# openSX70_ALPHA_V6-2-5-20181220.net
KiCad netlist of a schematic drawn in EAGLE
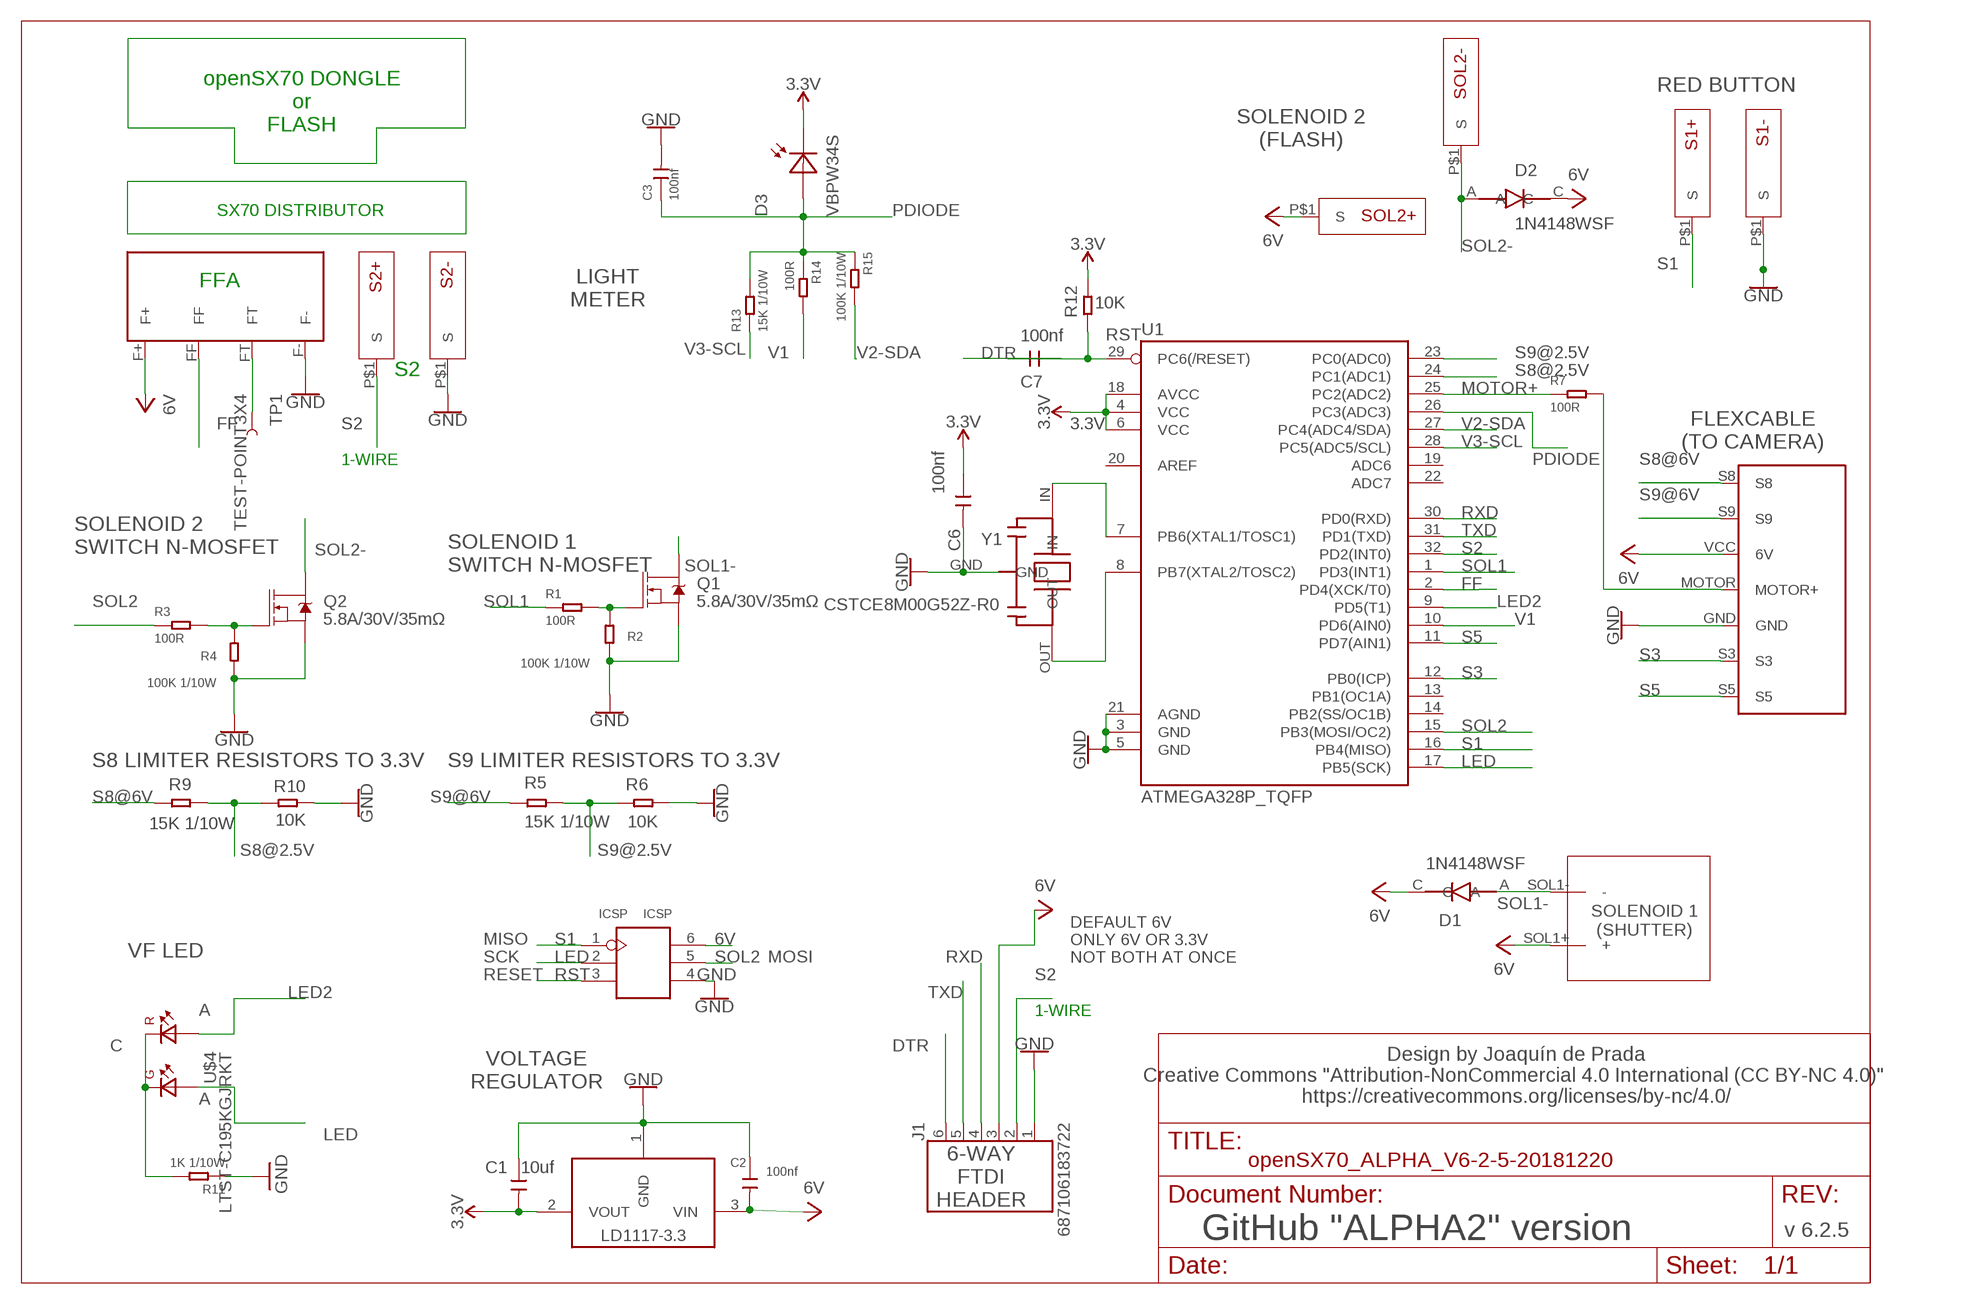
[diagram p0: schematic, sheet 1]

(export (version "E")
  (design (tool "Eeschema 10.0.6"))
  (components
    (comp (ref "C1")
      (value "10uf")
      (footprint "eagle-import:C0603")
      (fields (field (name "MPN") "CC0603KRX5R6BB106"))
      (libsource (lib "eagle-import") (part "CERAMIC-10UF-10V-10%-X5R(0603)"))
    )
    (comp (ref "C2")
      (value "100nf")
      (footprint "eagle-import:C0603")
      (fields (field (name "MPN") "CC0603KRX7R9BB104"))
      (libsource (lib "eagle-import") (part "CERAMIC-100NF-50V-10%-X7R(0603)"))
    )
    (comp (ref "C3")
      (value "100nf")
      (footprint "eagle-import:C0603")
      (fields (field (name "MPN") "CC0603KRX7R9BB104"))
      (libsource (lib "eagle-import") (part "CERAMIC-100NF-50V-10%-X7R(0603)"))
    )
    (comp (ref "C6")
      (value "100nf")
      (footprint "eagle-import:C0603")
      (fields (field (name "MPN") "CC0603KRX7R9BB104"))
      (libsource (lib "eagle-import") (part "CERAMIC-100NF-50V-10%-X7R(0603)"))
    )
    (comp (ref "C7")
      (value "100nf")
      (footprint "eagle-import:C0603")
      (fields (field (name "MPN") "CC0603KRX7R9BB104"))
      (libsource (lib "eagle-import") (part "CERAMIC-100NF-50V-10%-X7R(0603)"))
    )
    (comp (ref "D1")
      (value "1N4148WSF")
      (footprint "eagle-import:SODFL2512X100N")
      (fields (field (name "MANUFACTURER") "Fairchild Semiconductor"))
      (libsource (lib "eagle-import") (part "1N4148WS"))
    )
    (comp (ref "D2")
      (value "1N4148WSF")
      (footprint "eagle-import:SODFL2512X100N")
      (fields (field (name "MANUFACTURER") "Fairchild Semiconductor"))
      (libsource (lib "eagle-import") (part "1N4148WS"))
    )
    (comp (ref "D3")
      (value "VBPW34S")
      (footprint "eagle-import:SOD6439X130N")
      (fields (field (name "DIGI-KEY_PART_NUMBER") "751-1500-1-ND") (field (name "MF") "Vishay"))
      (libsource (lib "eagle-import") (part "VBPW34S"))
    )
    (comp (ref "ICSP")
      (value "ICSP")
      (footprint "eagle-import:H2X3-2.54")
      (libsource (lib "eagle-import") (part "ICSP"))
    )
    (comp (ref "J1")
      (value "687106183722")
      (footprint "eagle-import:687106183722")
      (fields (field (name "MF") "Wurth Electronics"))
      (libsource (lib "eagle-import") (part "687106183722"))
    )
    (comp (ref "LD11172.5V")
      (value "LD1117 2.5V")
      (footprint "eagle-import:SOT223")
      (fields (field (name "MF") "Advanced Monolithic Systems") (field (name "MP") "AMS1117-5.0"))
      (libsource (lib "eagle-import") (part "LD1117-3.3"))
    )
    (comp (ref "Q1")
      (value "5.8A/30V/35mΩ")
      (footprint "eagle-import:SOT23-3")
      (libsource (lib "eagle-import") (part "MOSFET-NCH-AO3404A"))
    )
    (comp (ref "Q2")
      (value "5.8A/30V/35mΩ")
      (footprint "eagle-import:SOT23-3")
      (libsource (lib "eagle-import") (part "MOSFET-NCH-AO3404A"))
    )
    (comp (ref "R1")
      (value "100R")
      (footprint "eagle-import:R0603")
      (fields (field (name "MPN") "RC0603JR-07100RL"))
      (libsource (lib "eagle-import") (part "SMD-RES-100R-5%-1/10W(0603)"))
    )
    (comp (ref "R2")
      (value "100K 1/10W")
      (footprint "eagle-import:R0603")
      (fields (field (name "MPN") "RC0603JR-07100KL"))
      (libsource (lib "eagle-import") (part "SMD-RES-100K-5%-1/10W(0603)"))
    )
    (comp (ref "R3")
      (value "100R")
      (footprint "eagle-import:R0603")
      (fields (field (name "MPN") "RC0603JR-07100RL"))
      (libsource (lib "eagle-import") (part "SMD-RES-100R-5%-1/10W(0603)"))
    )
    (comp (ref "R4")
      (value "100K 1/10W")
      (footprint "eagle-import:R0603")
      (fields (field (name "MPN") "RC0603JR-07100KL"))
      (libsource (lib "eagle-import") (part "SMD-RES-100K-5%-1/10W(0603)"))
    )
    (comp (ref "R5")
      (value "15K 1/10W")
      (footprint "eagle-import:R0603")
      (fields (field (name "MPN") "RC0603FR-0715KL"))
      (libsource (lib "eagle-import") (part "SMD-RES-15K-1%-1/10W(0603)"))
    )
    (comp (ref "R6")
      (value "10K")
      (footprint "eagle-import:R0603")
      (fields (field (name "MPN") "RC0603FR-0710KL"))
      (libsource (lib "eagle-import") (part "SMD-RES-10K-1%-1/10W(0603)"))
    )
    (comp (ref "R7")
      (value "100R")
      (footprint "eagle-import:R0603")
      (fields (field (name "MPN") "RC0603JR-07100RL"))
      (libsource (lib "eagle-import") (part "SMD-RES-100R-5%-1/10W(0603)"))
    )
    (comp (ref "R9")
      (value "15K 1/10W")
      (footprint "eagle-import:R0603")
      (fields (field (name "MPN") "RC0603FR-0715KL"))
      (libsource (lib "eagle-import") (part "SMD-RES-15K-1%-1/10W(0603)"))
    )
    (comp (ref "R10")
      (value "10K")
      (footprint "eagle-import:R0603")
      (fields (field (name "MPN") "RC0603FR-0710KL"))
      (libsource (lib "eagle-import") (part "SMD-RES-10K-1%-1/10W(0603)"))
    )
    (comp (ref "R11")
      (value "1K 1/10W")
      (footprint "eagle-import:R0603")
      (fields (field (name "MPN") "RC0603JR-071KL"))
      (libsource (lib "eagle-import") (part "SMD-RES-1K-5%-1/10W(0603)"))
    )
    (comp (ref "R12")
      (value "10K")
      (footprint "eagle-import:R0603")
      (fields (field (name "MPN") "RC0603FR-0710KL"))
      (libsource (lib "eagle-import") (part "SMD-RES-10K-1%-1/10W(0603)"))
    )
    (comp (ref "R13")
      (value "15K 1/10W")
      (footprint "eagle-import:R0603")
      (fields (field (name "MPN") "RC0603FR-0715KL"))
      (libsource (lib "eagle-import") (part "SMD-RES-15K-1%-1/10W(0603)"))
    )
    (comp (ref "R14")
      (value "100R")
      (footprint "eagle-import:R0603")
      (fields (field (name "MPN") "RC0603JR-07100RL"))
      (libsource (lib "eagle-import") (part "SMD-RES-100R-5%-1/10W(0603)"))
    )
    (comp (ref "R15")
      (value "100K 1/10W")
      (footprint "eagle-import:R0603")
      (fields (field (name "MPN") "RC0603JR-07100KL"))
      (libsource (lib "eagle-import") (part "SMD-RES-100K-5%-1/10W(0603)"))
    )
    (comp (ref "S1+")
      (value "SX70-S-PAD-NEW")
      (footprint "eagle-import:SX70-S-PAD2")
      (libsource (lib "eagle-import") (part "SX70-S-PAD-NEW"))
    )
    (comp (ref "S1-")
      (value "SX70-S-PAD-NEW")
      (footprint "eagle-import:SX70-S-PAD2")
      (libsource (lib "eagle-import") (part "SX70-S-PAD-NEW"))
    )
    (comp (ref "S2+")
      (value "SX70-S-PAD-NEW")
      (footprint "eagle-import:SX70-S-PAD2")
      (libsource (lib "eagle-import") (part "SX70-S-PAD-NEW"))
    )
    (comp (ref "S2-")
      (value "SX70-S-PAD-NEW")
      (footprint "eagle-import:SX70-S-PAD2")
      (libsource (lib "eagle-import") (part "SX70-S-PAD-NEW"))
    )
    (comp (ref "SOL1")
      (value "SX70-SOLENOID1-2PADS")
      (footprint "eagle-import:SX70-SOLENOID1-2")
      (libsource (lib "eagle-import") (part "SX70-SOLENOID1-2PADS"))
    )
    (comp (ref "SOL2+")
      (value "SX70-S-PAD-NEW")
      (footprint "eagle-import:SX70-S-PAD2")
      (libsource (lib "eagle-import") (part "SX70-S-PAD-NEW"))
    )
    (comp (ref "SOL2-")
      (value "SX70-S-PAD-NEW")
      (footprint "eagle-import:SX70-S-PAD2")
      (libsource (lib "eagle-import") (part "SX70-S-PAD-NEW"))
    )
    (comp (ref "TP1")
      (value "TEST-POINT3X4")
      (footprint "eagle-import:PAD.03X.04")
      (libsource (lib "eagle-import") (part "TEST-POINT3X4"))
    )
    (comp (ref "U$1")
      (value "SX70-7-PAD")
      (footprint "eagle-import:SX70-7-PAD-PROPER")
      (libsource (lib "eagle-import") (part "SX70-7-PAD"))
    )
    (comp (ref "U$2")
      (value "FFA")
      (footprint "eagle-import:FFA-PAD-PACKAGE")
      (libsource (lib "eagle-import") (part "SX70-FFA-PAD"))
    )
    (comp (ref "U$4")
      (value "LTST-C195KGJRKT")
      (footprint "eagle-import:LTST-BILED-15X16")
      (fields (field (name "MF") "Lite-On Inc."))
      (libsource (lib "eagle-import") (part "LTST-C195KGJRKT"))
    )
    (comp (ref "U1")
      (value "ATMEGA328P_TQFP")
      (footprint "eagle-import:TQFP32-08")
      (libsource (lib "eagle-import") (part "ATMEGA328P_TQFP"))
    )
    (comp (ref "Y1")
      (value "CSTCE8M00G52Z-R0")
      (footprint "eagle-import:CFP95P160X100-3N")
      (fields (field (name "MF") "Murata") (field (name "MP") "CSTCE16M0V53-R0"))
      (libsource (lib "eagle-import") (part "CSTCE16M0V53-R0"))
    )
  )
  (nets
    (net (code "1") (name "/DTR") (class "Default")
      (node (ref "C7") (pin "1") (pinfunction "1_1") (pintype "passive"))
      (node (ref "J1") (pin "6") (pinfunction "1_6") (pintype "passive"))
    )
    (net (code "2") (name "/FF") (class "Default")
      (node (ref "U$2") (pin "FF") (pinfunction "FF_FF") (pintype "bidirectional"))
      (node (ref "U1") (pin "2") (pinfunction "PD4(XCK/T0)_2") (pintype "bidirectional"))
    )
    (net (code "3") (name "/LED") (class "Default")
      (node (ref "ICSP") (pin "2") (pinfunction "SCK_2") (pintype "bidirectional"))
      (node (ref "U$4") (pin "P$1") (pinfunction "A1_P$1") (pintype "passive"))
      (node (ref "U1") (pin "17") (pinfunction "PB5(SCK)_17") (pintype "bidirectional"))
    )
    (net (code "4") (name "/LED2") (class "Default")
      (node (ref "U$4") (pin "P$2") (pinfunction "A2_P$2") (pintype "passive"))
      (node (ref "U1") (pin "9") (pinfunction "PD5(T1)_9") (pintype "bidirectional"))
    )
    (net (code "5") (name "/MOTOR+") (class "Default")
      (node (ref "R7") (pin "1") (pinfunction "1_1") (pintype "passive"))
      (node (ref "U1") (pin "25") (pinfunction "PC2(ADC2)_25") (pintype "bidirectional"))
    )
    (net (code "6") (name "/PDIODE") (class "Default")
      (node (ref "C3") (pin "1") (pinfunction "1_1") (pintype "passive"))
      (node (ref "D3") (pin "A") (pinfunction "A_A") (pintype "passive"))
      (node (ref "R13") (pin "2") (pinfunction "2_2") (pintype "passive"))
      (node (ref "R14") (pin "1") (pinfunction "1_1") (pintype "passive"))
      (node (ref "R15") (pin "1") (pinfunction "1_1") (pintype "passive"))
      (node (ref "U1") (pin "26") (pinfunction "PC3(ADC3)_26") (pintype "bidirectional"))
    )
    (net (code "7") (name "/RST") (class "Default")
      (node (ref "C7") (pin "2") (pinfunction "2_2") (pintype "passive"))
      (node (ref "ICSP") (pin "3") (pinfunction "RST_3") (pintype "bidirectional"))
      (node (ref "R12") (pin "1") (pinfunction "1_1") (pintype "passive"))
      (node (ref "U1") (pin "29") (pinfunction "PC6(/RESET)_29") (pintype "bidirectional"))
    )
    (net (code "8") (name "/RXD") (class "Default")
      (node (ref "J1") (pin "4") (pinfunction "3_4") (pintype "passive"))
      (node (ref "U1") (pin "30") (pinfunction "PD0(RXD)_30") (pintype "bidirectional"))
    )
    (net (code "9") (name "/S1") (class "Default")
      (node (ref "ICSP") (pin "1") (pinfunction "MISO_1") (pintype "bidirectional"))
      (node (ref "S1+") (pin "P$1") (pinfunction "S_P$1") (pintype "bidirectional"))
      (node (ref "U1") (pin "16") (pinfunction "PB4(MISO)_16") (pintype "bidirectional"))
    )
    (net (code "10") (name "/S2") (class "Default")
      (node (ref "J1") (pin "2") (pinfunction "5_2") (pintype "passive"))
      (node (ref "S2+") (pin "P$1") (pinfunction "S_P$1") (pintype "bidirectional"))
      (node (ref "U1") (pin "32") (pinfunction "PD2(INT0)_32") (pintype "bidirectional"))
    )
    (net (code "11") (name "/S3") (class "Default")
      (node (ref "U$1") (pin "S3") (pinfunction "S3_S3") (pintype "bidirectional"))
      (node (ref "U1") (pin "12") (pinfunction "PB0(ICP)_12") (pintype "bidirectional"))
    )
    (net (code "12") (name "/S5") (class "Default")
      (node (ref "U$1") (pin "S5") (pinfunction "S5_S5") (pintype "bidirectional"))
      (node (ref "U1") (pin "11") (pinfunction "PD7(AIN1)_11") (pintype "bidirectional"))
    )
    (net (code "13") (name "/S8@2.5V") (class "Default")
      (node (ref "R10") (pin "1") (pinfunction "1_1") (pintype "passive"))
      (node (ref "R9") (pin "2") (pinfunction "2_2") (pintype "passive"))
      (node (ref "U1") (pin "24") (pinfunction "PC1(ADC1)_24") (pintype "bidirectional"))
    )
    (net (code "14") (name "/S8@6V") (class "Default")
      (node (ref "R9") (pin "1") (pinfunction "1_1") (pintype "passive"))
      (node (ref "U$1") (pin "S8") (pinfunction "S8_S8") (pintype "bidirectional"))
    )
    (net (code "15") (name "/S9@2.5V") (class "Default")
      (node (ref "R5") (pin "2") (pinfunction "2_2") (pintype "passive"))
      (node (ref "R6") (pin "1") (pinfunction "1_1") (pintype "passive"))
      (node (ref "U1") (pin "23") (pinfunction "PC0(ADC0)_23") (pintype "bidirectional"))
    )
    (net (code "16") (name "/S9@6V") (class "Default")
      (node (ref "R5") (pin "1") (pinfunction "1_1") (pintype "passive"))
      (node (ref "U$1") (pin "S9") (pinfunction "S9_S9") (pintype "bidirectional"))
    )
    (net (code "17") (name "/SOL1") (class "Default")
      (node (ref "R1") (pin "1") (pinfunction "1_1") (pintype "passive"))
      (node (ref "U1") (pin "1") (pinfunction "PD3(INT1)_1") (pintype "bidirectional"))
    )
    (net (code "18") (name "/SOL1-") (class "Default")
      (node (ref "D1") (pin "A") (pinfunction "A_A") (pintype "passive"))
      (node (ref "Q1") (pin "3") (pinfunction "D_3") (pintype "bidirectional"))
      (node (ref "SOL1") (pin "SOL1-") (pinfunction "-_SOL1-") (pintype "bidirectional"))
    )
    (net (code "19") (name "/SOL2") (class "Default")
      (node (ref "ICSP") (pin "5") (pinfunction "MOSI_5") (pintype "bidirectional"))
      (node (ref "R3") (pin "1") (pinfunction "1_1") (pintype "passive"))
      (node (ref "U1") (pin "15") (pinfunction "PB3(MOSI/OC2)_15") (pintype "bidirectional"))
    )
    (net (code "20") (name "/SOL2-") (class "Default")
      (node (ref "D2") (pin "A") (pinfunction "A_A") (pintype "passive"))
      (node (ref "Q2") (pin "3") (pinfunction "D_3") (pintype "bidirectional"))
      (node (ref "SOL2-") (pin "P$1") (pinfunction "S_P$1") (pintype "bidirectional"))
    )
    (net (code "21") (name "/TXD") (class "Default")
      (node (ref "J1") (pin "5") (pinfunction "2_5") (pintype "passive"))
      (node (ref "U1") (pin "31") (pinfunction "PD1(TXD)_31") (pintype "bidirectional"))
    )
    (net (code "22") (name "/V1") (class "Default")
      (node (ref "R14") (pin "2") (pinfunction "2_2") (pintype "passive"))
      (node (ref "U1") (pin "10") (pinfunction "PD6(AIN0)_10") (pintype "bidirectional"))
    )
    (net (code "23") (name "/V2-SDA") (class "Default")
      (node (ref "R15") (pin "2") (pinfunction "2_2") (pintype "passive"))
      (node (ref "U1") (pin "27") (pinfunction "PC4(ADC4/SDA)_27") (pintype "bidirectional"))
    )
    (net (code "24") (name "/V3-SCL") (class "Default")
      (node (ref "R13") (pin "1") (pinfunction "1_1") (pintype "passive"))
      (node (ref "U1") (pin "28") (pinfunction "PC5(ADC5/SCL)_28") (pintype "bidirectional"))
    )
    (net (code "25") (name "3.3V") (class "Default")
      (node (ref "C1") (pin "2") (pinfunction "2_2") (pintype "passive"))
      (node (ref "C6") (pin "1") (pinfunction "1_1") (pintype "passive"))
      (node (ref "D3") (pin "C") (pinfunction "C_C") (pintype "passive"))
      (node (ref "LD11172.5V") (pin "2") (pinfunction "VOUT_2") (pintype "bidirectional"))
      (node (ref "R12") (pin "2") (pinfunction "2_2") (pintype "passive"))
      (node (ref "U1") (pin "18") (pinfunction "AVCC_18") (pintype "bidirectional"))
      (node (ref "U1") (pin "4") (pinfunction "VCC_4") (pintype "bidirectional"))
      (node (ref "U1") (pin "6") (pinfunction "VCC_6") (pintype "bidirectional"))
    )
    (net (code "26") (name "6V") (class "Default")
      (node (ref "C2") (pin "2") (pinfunction "2_2") (pintype "passive"))
      (node (ref "D1") (pin "C") (pinfunction "C_C") (pintype "passive"))
      (node (ref "D2") (pin "C") (pinfunction "C_C") (pintype "passive"))
      (node (ref "ICSP") (pin "6") (pinfunction "VCC_6") (pintype "bidirectional"))
      (node (ref "J1") (pin "3") (pinfunction "4_3") (pintype "passive"))
      (node (ref "LD11172.5V") (pin "3") (pinfunction "VIN_3") (pintype "bidirectional"))
      (node (ref "SOL1") (pin "SOL1+") (pinfunction "+_SOL1+") (pintype "bidirectional"))
      (node (ref "SOL2+") (pin "P$1") (pinfunction "S_P$1") (pintype "bidirectional"))
      (node (ref "U$1") (pin "VCC") (pinfunction "6V_VCC") (pintype "bidirectional"))
      (node (ref "U$2") (pin "F+") (pinfunction "F+_F+") (pintype "bidirectional"))
    )
    (net (code "27") (name "GND") (class "Default")
      (node (ref "C1") (pin "1") (pinfunction "1_1") (pintype "passive"))
      (node (ref "C2") (pin "1") (pinfunction "1_1") (pintype "passive"))
      (node (ref "C3") (pin "2") (pinfunction "2_2") (pintype "passive"))
      (node (ref "C6") (pin "2") (pinfunction "2_2") (pintype "passive"))
      (node (ref "ICSP") (pin "4") (pinfunction "GND_4") (pintype "bidirectional"))
      (node (ref "J1") (pin "1") (pinfunction "6_1") (pintype "passive"))
      (node (ref "LD11172.5V") (pin "1") (pinfunction "GND_1") (pintype "bidirectional"))
      (node (ref "Q1") (pin "2") (pinfunction "S_2") (pintype "bidirectional"))
      (node (ref "Q2") (pin "2") (pinfunction "S_2") (pintype "bidirectional"))
      (node (ref "R10") (pin "2") (pinfunction "2_2") (pintype "passive"))
      (node (ref "R11") (pin "1") (pinfunction "1_1") (pintype "passive"))
      (node (ref "R2") (pin "1") (pinfunction "1_1") (pintype "passive"))
      (node (ref "R4") (pin "1") (pinfunction "1_1") (pintype "passive"))
      (node (ref "R6") (pin "2") (pinfunction "2_2") (pintype "passive"))
      (node (ref "S1-") (pin "P$1") (pinfunction "S_P$1") (pintype "bidirectional"))
      (node (ref "S2-") (pin "P$1") (pinfunction "S_P$1") (pintype "bidirectional"))
      (node (ref "U$1") (pin "GND") (pinfunction "GND_GND") (pintype "bidirectional"))
      (node (ref "U$2") (pin "F-") (pinfunction "F-_F-") (pintype "bidirectional"))
      (node (ref "U1") (pin "21") (pinfunction "AGND_21") (pintype "bidirectional"))
      (node (ref "U1") (pin "3") (pinfunction "GND_3") (pintype "bidirectional"))
      (node (ref "U1") (pin "5") (pinfunction "GND_5") (pintype "bidirectional"))
      (node (ref "Y1") (pin "GND") (pinfunction "GND_GND") (pintype "passive"))
    )
    (net (code "28") (name "Net-(Q1-G)") (class "Default")
      (node (ref "Q1") (pin "1") (pinfunction "G_1") (pintype "bidirectional"))
      (node (ref "R1") (pin "2") (pinfunction "2_2") (pintype "passive"))
      (node (ref "R2") (pin "2") (pinfunction "2_2") (pintype "passive"))
    )
    (net (code "29") (name "Net-(Q2-G)") (class "Default")
      (node (ref "Q2") (pin "1") (pinfunction "G_1") (pintype "bidirectional"))
      (node (ref "R3") (pin "2") (pinfunction "2_2") (pintype "passive"))
      (node (ref "R4") (pin "2") (pinfunction "2_2") (pintype "passive"))
    )
    (net (code "30") (name "Net-(TP1-1)") (class "Default")
      (node (ref "TP1") (pin "P$1") (pinfunction "1_P$1") (pintype "bidirectional"))
      (node (ref "U$2") (pin "FT") (pinfunction "FT_FT") (pintype "bidirectional"))
    )
    (net (code "31") (name "Net-(U$1-MOTOR+)") (class "Default")
      (node (ref "R7") (pin "2") (pinfunction "2_2") (pintype "passive"))
      (node (ref "U$1") (pin "MOTOR") (pinfunction "MOTOR+_MOTOR") (pintype "bidirectional"))
    )
    (net (code "32") (name "Net-(U$4-K1)") (class "Default")
      (node (ref "R11") (pin "2") (pinfunction "2_2") (pintype "passive"))
      (node (ref "U$4") (pin "P$3") (pinfunction "K1_P$3") (pintype "passive"))
      (node (ref "U$4") (pin "P$4") (pinfunction "K2_P$4") (pintype "passive"))
    )
    (net (code "33") (name "Net-(U1-PB6(XTAL1{slash}TOSC1))") (class "Default")
      (node (ref "U1") (pin "7") (pinfunction "PB6(XTAL1/TOSC1)_7") (pintype "bidirectional"))
      (node (ref "Y1") (pin "IN") (pinfunction "IN_IN") (pintype "input"))
    )
    (net (code "34") (name "Net-(U1-PB7(XTAL2{slash}TOSC2))") (class "Default")
      (node (ref "U1") (pin "8") (pinfunction "PB7(XTAL2/TOSC2)_8") (pintype "bidirectional"))
      (node (ref "Y1") (pin "OUT") (pinfunction "OUT_OUT") (pintype "output"))
    )
    (net (code "35") (name "unconnected-(U1-ADC6-Pad19)") (class "Default")
      (node (ref "U1") (pin "19") (pinfunction "ADC6_19") (pintype "bidirectional"))
    )
    (net (code "36") (name "unconnected-(U1-ADC7-Pad22)") (class "Default")
      (node (ref "U1") (pin "22") (pinfunction "ADC7_22") (pintype "bidirectional"))
    )
    (net (code "37") (name "unconnected-(U1-AREF-Pad20)") (class "Default")
      (node (ref "U1") (pin "20") (pinfunction "AREF_20") (pintype "bidirectional"))
    )
    (net (code "38") (name "unconnected-(U1-PB1(OC1A)-Pad13)") (class "Default")
      (node (ref "U1") (pin "13") (pinfunction "PB1(OC1A)_13") (pintype "bidirectional"))
    )
    (net (code "39") (name "unconnected-(U1-PB2(SS{slash}OC1B)-Pad14)") (class "Default")
      (node (ref "U1") (pin "14") (pinfunction "PB2(SS/OC1B)_14") (pintype "bidirectional"))
    )
  )
)
